# HydraBus_1_0_Rev1_2.net
KiCad netlist of a schematic drawn in EAGLE
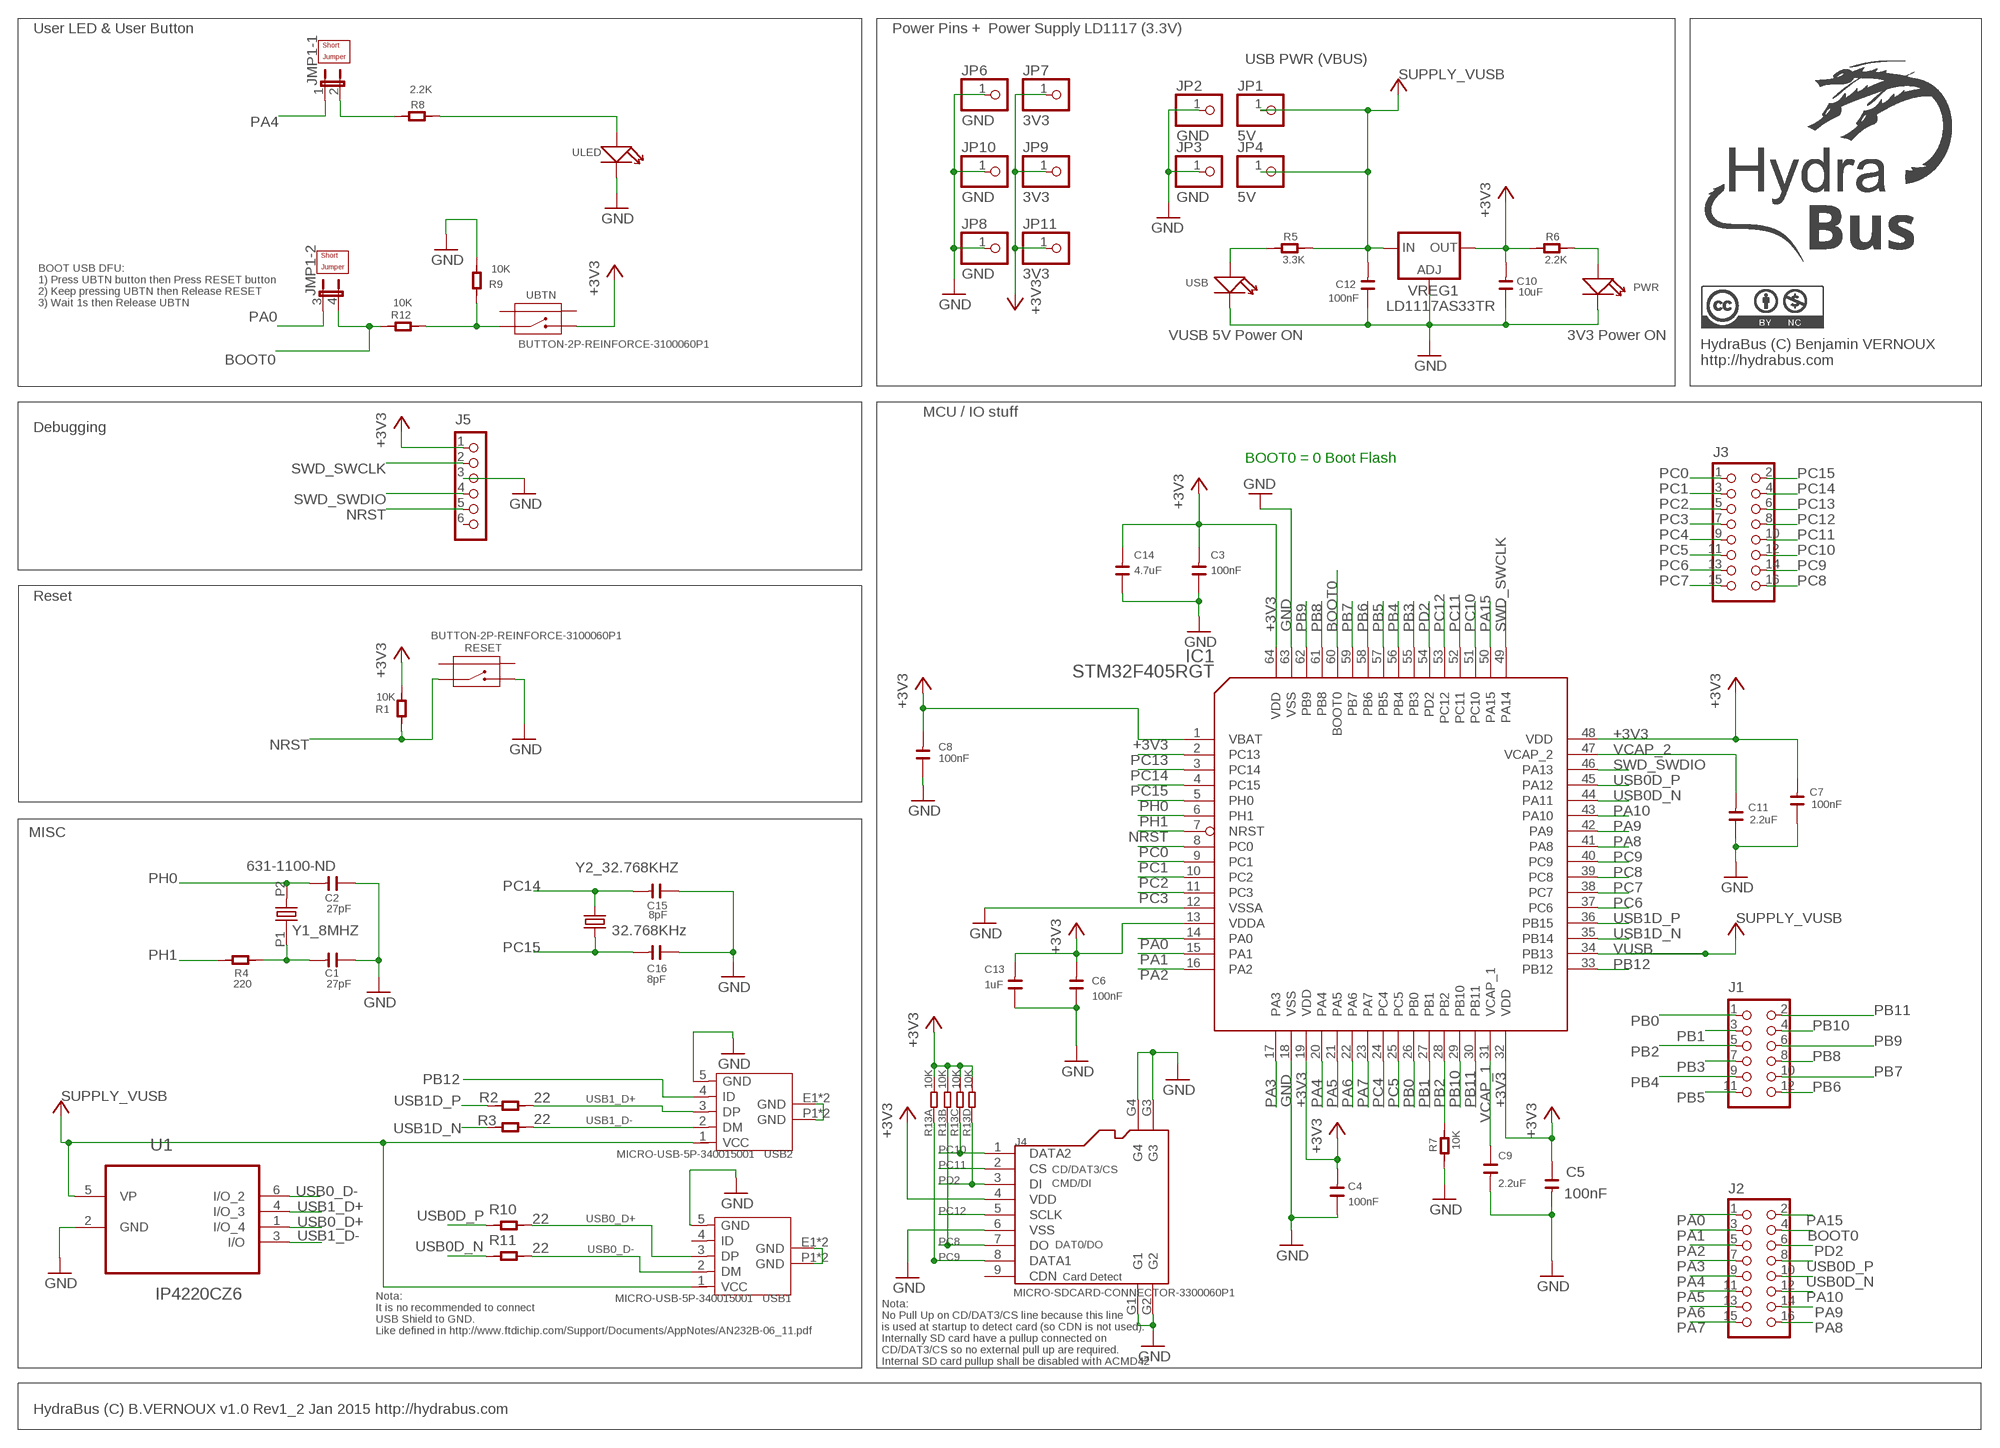
[diagram p0: schematic, sheet 1]

(export (version "E")
  (design (tool "Eeschema 10.0.6"))
  (components
    (comp (ref "C1")
      (value "27pF")
      (footprint "eagle-import:C0603")
      (libsource (lib "eagle-import") (part "C-0603"))
    )
    (comp (ref "C2")
      (value "27pF")
      (footprint "eagle-import:C0603")
      (libsource (lib "eagle-import") (part "C-0603"))
    )
    (comp (ref "C3")
      (value "100nF")
      (footprint "eagle-import:C0603")
      (libsource (lib "eagle-import") (part "C-0603"))
    )
    (comp (ref "C4")
      (value "100nF")
      (footprint "eagle-import:C0603")
      (libsource (lib "eagle-import") (part "C-0603"))
    )
    (comp (ref "C5")
      (value "100nF")
      (footprint "eagle-import:C0603")
      (libsource (lib "eagle-import") (part "C-0603"))
    )
    (comp (ref "C6")
      (value "100nF")
      (footprint "eagle-import:C0603")
      (libsource (lib "eagle-import") (part "C-0603"))
    )
    (comp (ref "C7")
      (value "100nF")
      (footprint "eagle-import:C0603")
      (libsource (lib "eagle-import") (part "C-0603"))
    )
    (comp (ref "C8")
      (value "100nF")
      (footprint "eagle-import:C0603")
      (libsource (lib "eagle-import") (part "C-0603"))
    )
    (comp (ref "C9")
      (value "2.2uF")
      (footprint "eagle-import:C0603")
      (libsource (lib "eagle-import") (part "C-0603"))
    )
    (comp (ref "C10")
      (value "10uF")
      (footprint "eagle-import:C0805")
      (libsource (lib "eagle-import") (part "C-0805"))
    )
    (comp (ref "C11")
      (value "2.2uF")
      (footprint "eagle-import:C0603")
      (libsource (lib "eagle-import") (part "C-0603"))
    )
    (comp (ref "C12")
      (value "100nF")
      (footprint "eagle-import:C0603")
      (libsource (lib "eagle-import") (part "C-0603"))
    )
    (comp (ref "C13")
      (value "1uF")
      (footprint "eagle-import:C0603")
      (libsource (lib "eagle-import") (part "C-0603"))
    )
    (comp (ref "C14")
      (value "4.7uF")
      (footprint "eagle-import:C0603")
      (libsource (lib "eagle-import") (part "C-0603"))
    )
    (comp (ref "C15")
      (value "8pF")
      (footprint "eagle-import:C0603")
      (libsource (lib "eagle-import") (part "C-0603"))
    )
    (comp (ref "C16")
      (value "8pF")
      (footprint "eagle-import:C0603")
      (libsource (lib "eagle-import") (part "C-0603"))
    )
    (comp (ref "IC1")
      (value "STM32F405RGT")
      (footprint "eagle-import:LQFP64")
      (libsource (lib "eagle-import") (part "STM32F405RTG"))
    )
    (comp (ref "J1")
      (value "CON_HEADER_2X06")
      (footprint "eagle-import:M2X6")
      (libsource (lib "eagle-import") (part "CON_HEADER_2X06"))
    )
    (comp (ref "J2")
      (value "CON_HEADER_2X08")
      (footprint "eagle-import:M2X8")
      (libsource (lib "eagle-import") (part "CON_HEADER_2X08"))
    )
    (comp (ref "J3")
      (value "CON_HEADER_2X08")
      (footprint "eagle-import:M2X8")
      (libsource (lib "eagle-import") (part "CON_HEADER_2X08"))
    )
    (comp (ref "J4")
      (value "MICRO-SDCARD-CONNECTOR-3300060P1")
      (footprint "eagle-import:9P-SMD-W-RING")
      (libsource (lib "eagle-import") (part "MICRO-SDCARD-CONNECTOR-3300060P1"))
    )
    (comp (ref "J5")
      (value "CON_HEADER_1X06-PTH")
      (footprint "eagle-import:M1X6")
      (libsource (lib "eagle-import") (part "CON_HEADER_1X06-PTH"))
    )
    (comp (ref "JMP1")
      (value "JP2QE")
      (footprint "eagle-import:JP2Q")
      (libsource (lib "eagle-import") (part "JP2QE"))
    )
    (comp (ref "JMP_UBTN")
      (value "SHORT-JUMPER-2P-3460440P1")
      (footprint "eagle-import:2P-2.54")
      (libsource (lib "eagle-import") (part "SHORT-JUMPER-2P-3460440P1"))
    )
    (comp (ref "JMP_ULED")
      (value "SHORT-JUMPER-2P-3460440P1")
      (footprint "eagle-import:2P-2.54")
      (libsource (lib "eagle-import") (part "SHORT-JUMPER-2P-3460440P1"))
    )
    (comp (ref "JP1")
      (value "5V")
      (footprint "eagle-import:1X01")
      (libsource (lib "eagle-import") (part "PINHD-1X1"))
    )
    (comp (ref "JP2")
      (value "GND")
      (footprint "eagle-import:1X01")
      (libsource (lib "eagle-import") (part "PINHD-1X1"))
    )
    (comp (ref "JP3")
      (value "GND")
      (footprint "eagle-import:1X01")
      (libsource (lib "eagle-import") (part "PINHD-1X1"))
    )
    (comp (ref "JP4")
      (value "5V")
      (footprint "eagle-import:1X01")
      (libsource (lib "eagle-import") (part "PINHD-1X1"))
    )
    (comp (ref "JP6")
      (value "GND")
      (footprint "eagle-import:1X01")
      (libsource (lib "eagle-import") (part "PINHD-1X1"))
    )
    (comp (ref "JP7")
      (value "3V3")
      (footprint "eagle-import:1X01")
      (libsource (lib "eagle-import") (part "PINHD-1X1"))
    )
    (comp (ref "JP8")
      (value "GND")
      (footprint "eagle-import:1X01")
      (libsource (lib "eagle-import") (part "PINHD-1X1"))
    )
    (comp (ref "JP9")
      (value "3V3")
      (footprint "eagle-import:1X01")
      (libsource (lib "eagle-import") (part "PINHD-1X1"))
    )
    (comp (ref "JP10")
      (value "GND")
      (footprint "eagle-import:1X01")
      (libsource (lib "eagle-import") (part "PINHD-1X1"))
    )
    (comp (ref "JP11")
      (value "3V3")
      (footprint "eagle-import:1X01")
      (libsource (lib "eagle-import") (part "PINHD-1X1"))
    )
    (comp (ref "PWR")
      (value "LED")
      (footprint "eagle-import:LED0603")
      (libsource (lib "eagle-import") (part "LED"))
    )
    (comp (ref "R1")
      (value "10K")
      (footprint "eagle-import:R0603")
      (libsource (lib "eagle-import") (part "R-0603"))
    )
    (comp (ref "R2")
      (value "22")
      (footprint "eagle-import:R0603")
      (libsource (lib "eagle-import") (part "R-0603"))
    )
    (comp (ref "R3")
      (value "22")
      (footprint "eagle-import:R0603")
      (libsource (lib "eagle-import") (part "R-0603"))
    )
    (comp (ref "R4")
      (value "220")
      (footprint "eagle-import:R0603")
      (libsource (lib "eagle-import") (part "R-0603"))
    )
    (comp (ref "R5")
      (value "3.3K")
      (footprint "eagle-import:R0603")
      (libsource (lib "eagle-import") (part "R-0603"))
    )
    (comp (ref "R6")
      (value "2.2K")
      (footprint "eagle-import:R0603")
      (libsource (lib "eagle-import") (part "R-0603"))
    )
    (comp (ref "R7")
      (value "10K")
      (footprint "eagle-import:R0603")
      (libsource (lib "eagle-import") (part "R-0603"))
    )
    (comp (ref "R8")
      (value "2.2K")
      (footprint "eagle-import:R0603")
      (libsource (lib "eagle-import") (part "R-0603"))
    )
    (comp (ref "R9")
      (value "10K")
      (footprint "eagle-import:R0603")
      (libsource (lib "eagle-import") (part "R-0603"))
    )
    (comp (ref "R10")
      (value "22")
      (footprint "eagle-import:R0603")
      (libsource (lib "eagle-import") (part "R-0603"))
    )
    (comp (ref "R11")
      (value "22")
      (footprint "eagle-import:R0603")
      (libsource (lib "eagle-import") (part "R-0603"))
    )
    (comp (ref "R12")
      (value "10K")
      (footprint "eagle-import:R0603")
      (libsource (lib "eagle-import") (part "R-0603"))
    )
    (comp (ref "R13")
      (value "10K")
      (footprint "eagle-import:R1206-8")
      (fields (field (name "OPL") "0040070P1 SMD RES ARRAY 10K OHM 4 RES 1206"))
      (libsource (lib "eagle-import") (part "R-4R"))
    )
    (comp (ref "RESET")
      (value "BUTTON-2P-REINFORCE-3100060P1")
      (footprint "eagle-import:4P-SMD-7.0X3.5X3.5H-90D")
      (libsource (lib "eagle-import") (part "BUTTON-2P-REINFORCE-3100060P1"))
    )
    (comp (ref "U1")
      (value "IP4220CZ6")
      (footprint "eagle-import:SOT95P275X110-6N")
      (libsource (lib "eagle-import") (part "IP4220CZ6"))
    )
    (comp (ref "UBTN")
      (value "BUTTON-2P-REINFORCE-3100060P1")
      (footprint "eagle-import:4P-SMD-7.0X3.5X3.5H-90D")
      (libsource (lib "eagle-import") (part "BUTTON-2P-REINFORCE-3100060P1"))
    )
    (comp (ref "ULED")
      (value "LED")
      (footprint "eagle-import:LED0603")
      (libsource (lib "eagle-import") (part "LED"))
    )
    (comp (ref "USB")
      (value "LED")
      (footprint "eagle-import:LED0603")
      (libsource (lib "eagle-import") (part "LED"))
    )
    (comp (ref "USB1")
      (value "MICRO-USB-5P-340015001")
      (footprint "eagle-import:B-SMD-5P")
      (libsource (lib "eagle-import") (part "MICRO-USB-5P-340015001"))
    )
    (comp (ref "USB2")
      (value "MICRO-USB-5P-340015001")
      (footprint "eagle-import:B-SMD-5P")
      (libsource (lib "eagle-import") (part "MICRO-USB-5P-340015001"))
    )
    (comp (ref "VREG1")
      (value "LD1117AS33TR")
      (footprint "eagle-import:SOT223")
      (libsource (lib "eagle-import") (part "LD117A?S33TR"))
    )
    (comp (ref "Y1_8MHZ")
      (value "631-1100-ND")
      (footprint "eagle-import:HC-49U-PTH")
      (libsource (lib "eagle-import") (part "OSC-XTAL-HC-49U-PTH"))
    )
    (comp (ref "Y2_32.768KHZ")
      (value "32.768KHz")
      (footprint "eagle-import:TC38H")
      (libsource (lib "eagle-import") (part "CRYSTALTC38H"))
    )
  )
  (nets
    (net (code "1") (name "+3V3") (class "Default")
      (node (ref "C10") (pin "1") (pinfunction "1_1") (pintype "bidirectional"))
      (node (ref "C13") (pin "1") (pinfunction "1_1") (pintype "bidirectional"))
      (node (ref "C14") (pin "1") (pinfunction "1_1") (pintype "bidirectional"))
      (node (ref "C3") (pin "1") (pinfunction "1_1") (pintype "bidirectional"))
      (node (ref "C4") (pin "1") (pinfunction "1_1") (pintype "bidirectional"))
      (node (ref "C5") (pin "2") (pinfunction "2_2") (pintype "bidirectional"))
      (node (ref "C6") (pin "1") (pinfunction "1_1") (pintype "bidirectional"))
      (node (ref "C7") (pin "1") (pinfunction "1_1") (pintype "bidirectional"))
      (node (ref "C8") (pin "1") (pinfunction "1_1") (pintype "bidirectional"))
      (node (ref "IC1") (pin "1") (pinfunction "VBAT_1") (pintype "power_in"))
      (node (ref "IC1") (pin "13") (pinfunction "VDDA_13") (pintype "power_in"))
      (node (ref "IC1") (pin "19") (pinfunction "VDD_19") (pintype "power_in"))
      (node (ref "IC1") (pin "32") (pinfunction "VDD_32") (pintype "power_in"))
      (node (ref "IC1") (pin "48") (pinfunction "VDD_48") (pintype "power_in"))
      (node (ref "IC1") (pin "64") (pinfunction "VDD_64") (pintype "power_in"))
      (node (ref "J4") (pin "4") (pinfunction "VDD_4") (pintype "bidirectional"))
      (node (ref "J5") (pin "1") (pinfunction "1_1") (pintype "bidirectional"))
      (node (ref "JP11") (pin "1") (pinfunction "1_1") (pintype "passive"))
      (node (ref "JP7") (pin "1") (pinfunction "1_1") (pintype "passive"))
      (node (ref "JP9") (pin "1") (pinfunction "1_1") (pintype "passive"))
      (node (ref "R1") (pin "2") (pinfunction "2_2") (pintype "bidirectional"))
      (node (ref "R13") (pin "5") (pinfunction "2_5") (pintype "passive"))
      (node (ref "R13") (pin "6") (pinfunction "2_6") (pintype "passive"))
      (node (ref "R13") (pin "7") (pinfunction "2_7") (pintype "passive"))
      (node (ref "R13") (pin "8") (pinfunction "2_8") (pintype "passive"))
      (node (ref "R6") (pin "2") (pinfunction "2_2") (pintype "bidirectional"))
      (node (ref "UBTN") (pin "2") (pinfunction "2_2") (pintype "bidirectional"))
      (node (ref "VREG1") (pin "4") (pinfunction "OUT_4") (pintype "passive"))
    )
    (net (code "2") (name "/BOOT0") (class "Default")
      (node (ref "IC1") (pin "60") (pinfunction "BOOT0_60") (pintype "bidirectional"))
      (node (ref "J2") (pin "4") (pinfunction "4_4") (pintype "passive"))
      (node (ref "JMP1") (pin "4") (pinfunction "2_4") (pintype "passive"))
      (node (ref "R12") (pin "2") (pinfunction "2_2") (pintype "bidirectional"))
    )
    (net (code "3") (name "/NRST") (class "Default")
      (node (ref "IC1") (pin "7") (pinfunction "NRST_7") (pintype "input"))
      (node (ref "J5") (pin "5") (pinfunction "5_5") (pintype "passive"))
      (node (ref "R1") (pin "1") (pinfunction "1_1") (pintype "bidirectional"))
      (node (ref "RESET") (pin "1") (pinfunction "1_1") (pintype "bidirectional"))
    )
    (net (code "4") (name "/PA0") (class "Default")
      (node (ref "IC1") (pin "14") (pinfunction "PA0_14") (pintype "bidirectional"))
      (node (ref "J2") (pin "1") (pinfunction "1_1") (pintype "passive"))
      (node (ref "JMP1") (pin "3") (pinfunction "1_3") (pintype "passive"))
    )
    (net (code "5") (name "/PA1") (class "Default")
      (node (ref "IC1") (pin "15") (pinfunction "PA1_15") (pintype "bidirectional"))
      (node (ref "J2") (pin "3") (pinfunction "3_3") (pintype "passive"))
    )
    (net (code "6") (name "/PA2") (class "Default")
      (node (ref "IC1") (pin "16") (pinfunction "PA2_16") (pintype "bidirectional"))
      (node (ref "J2") (pin "5") (pinfunction "5_5") (pintype "passive"))
    )
    (net (code "7") (name "/PA3") (class "Default")
      (node (ref "IC1") (pin "17") (pinfunction "PA3_17") (pintype "bidirectional"))
      (node (ref "J2") (pin "7") (pinfunction "7_7") (pintype "passive"))
    )
    (net (code "8") (name "/PA4") (class "Default")
      (node (ref "IC1") (pin "20") (pinfunction "PA4_20") (pintype "bidirectional"))
      (node (ref "J2") (pin "9") (pinfunction "9_9") (pintype "passive"))
      (node (ref "JMP1") (pin "1") (pinfunction "1_1") (pintype "passive"))
    )
    (net (code "9") (name "/PA5") (class "Default")
      (node (ref "IC1") (pin "21") (pinfunction "PA5_21") (pintype "bidirectional"))
      (node (ref "J2") (pin "11") (pinfunction "11_11") (pintype "passive"))
    )
    (net (code "10") (name "/PA6") (class "Default")
      (node (ref "IC1") (pin "22") (pinfunction "PA6_22") (pintype "bidirectional"))
      (node (ref "J2") (pin "13") (pinfunction "13_13") (pintype "passive"))
    )
    (net (code "11") (name "/PA7") (class "Default")
      (node (ref "IC1") (pin "23") (pinfunction "PA7_23") (pintype "bidirectional"))
      (node (ref "J2") (pin "15") (pinfunction "15_15") (pintype "passive"))
    )
    (net (code "12") (name "/PA8") (class "Default")
      (node (ref "IC1") (pin "41") (pinfunction "PA8_41") (pintype "bidirectional"))
      (node (ref "J2") (pin "16") (pinfunction "16_16") (pintype "passive"))
    )
    (net (code "13") (name "/PA9") (class "Default")
      (node (ref "IC1") (pin "42") (pinfunction "PA9_42") (pintype "bidirectional"))
      (node (ref "J2") (pin "14") (pinfunction "14_14") (pintype "passive"))
    )
    (net (code "14") (name "/PA10") (class "Default")
      (node (ref "IC1") (pin "43") (pinfunction "PA10_43") (pintype "bidirectional"))
      (node (ref "J2") (pin "12") (pinfunction "12_12") (pintype "passive"))
    )
    (net (code "15") (name "/PA15") (class "Default")
      (node (ref "IC1") (pin "50") (pinfunction "PA15_50") (pintype "bidirectional"))
      (node (ref "J2") (pin "2") (pinfunction "2_2") (pintype "passive"))
    )
    (net (code "16") (name "/PB0") (class "Default")
      (node (ref "IC1") (pin "26") (pinfunction "PB0_26") (pintype "bidirectional"))
      (node (ref "J1") (pin "1") (pinfunction "1_1") (pintype "passive"))
    )
    (net (code "17") (name "/PB1") (class "Default")
      (node (ref "IC1") (pin "27") (pinfunction "PB1_27") (pintype "bidirectional"))
      (node (ref "J1") (pin "3") (pinfunction "3_3") (pintype "passive"))
    )
    (net (code "18") (name "/PB2") (class "Default")
      (node (ref "IC1") (pin "28") (pinfunction "PB2_28") (pintype "bidirectional"))
      (node (ref "J1") (pin "5") (pinfunction "5_5") (pintype "passive"))
      (node (ref "R7") (pin "1") (pinfunction "1_1") (pintype "bidirectional"))
    )
    (net (code "19") (name "/PB3") (class "Default")
      (node (ref "IC1") (pin "55") (pinfunction "PB3_55") (pintype "bidirectional"))
      (node (ref "J1") (pin "7") (pinfunction "7_7") (pintype "passive"))
    )
    (net (code "20") (name "/PB4") (class "Default")
      (node (ref "IC1") (pin "56") (pinfunction "PB4_56") (pintype "bidirectional"))
      (node (ref "J1") (pin "9") (pinfunction "9_9") (pintype "passive"))
    )
    (net (code "21") (name "/PB5") (class "Default")
      (node (ref "IC1") (pin "57") (pinfunction "PB5_57") (pintype "bidirectional"))
      (node (ref "J1") (pin "11") (pinfunction "11_11") (pintype "passive"))
    )
    (net (code "22") (name "/PB6") (class "Default")
      (node (ref "IC1") (pin "58") (pinfunction "PB6_58") (pintype "bidirectional"))
      (node (ref "J1") (pin "12") (pinfunction "12_12") (pintype "passive"))
    )
    (net (code "23") (name "/PB7") (class "Default")
      (node (ref "IC1") (pin "59") (pinfunction "PB7_59") (pintype "bidirectional"))
      (node (ref "J1") (pin "10") (pinfunction "10_10") (pintype "passive"))
    )
    (net (code "24") (name "/PB8") (class "Default")
      (node (ref "IC1") (pin "61") (pinfunction "PB8_61") (pintype "bidirectional"))
      (node (ref "J1") (pin "8") (pinfunction "8_8") (pintype "passive"))
    )
    (net (code "25") (name "/PB9") (class "Default")
      (node (ref "IC1") (pin "62") (pinfunction "PB9_62") (pintype "bidirectional"))
      (node (ref "J1") (pin "6") (pinfunction "6_6") (pintype "passive"))
    )
    (net (code "26") (name "/PB10") (class "Default")
      (node (ref "IC1") (pin "29") (pinfunction "PB10_29") (pintype "bidirectional"))
      (node (ref "J1") (pin "4") (pinfunction "4_4") (pintype "passive"))
    )
    (net (code "27") (name "/PB11") (class "Default")
      (node (ref "IC1") (pin "30") (pinfunction "PB11_30") (pintype "bidirectional"))
      (node (ref "J1") (pin "2") (pinfunction "2_2") (pintype "passive"))
    )
    (net (code "28") (name "/PB12") (class "Default")
      (node (ref "IC1") (pin "33") (pinfunction "PB12_33") (pintype "bidirectional"))
      (node (ref "USB2") (pin "4") (pinfunction "ID_4") (pintype "bidirectional"))
    )
    (net (code "29") (name "/PC0") (class "Default")
      (node (ref "IC1") (pin "8") (pinfunction "PC0_8") (pintype "bidirectional"))
      (node (ref "J3") (pin "1") (pinfunction "1_1") (pintype "passive"))
    )
    (net (code "30") (name "/PC1") (class "Default")
      (node (ref "IC1") (pin "9") (pinfunction "PC1_9") (pintype "bidirectional"))
      (node (ref "J3") (pin "3") (pinfunction "3_3") (pintype "passive"))
    )
    (net (code "31") (name "/PC2") (class "Default")
      (node (ref "IC1") (pin "10") (pinfunction "PC2_10") (pintype "bidirectional"))
      (node (ref "J3") (pin "5") (pinfunction "5_5") (pintype "passive"))
    )
    (net (code "32") (name "/PC3") (class "Default")
      (node (ref "IC1") (pin "11") (pinfunction "PC3_11") (pintype "bidirectional"))
      (node (ref "J3") (pin "7") (pinfunction "7_7") (pintype "passive"))
    )
    (net (code "33") (name "/PC4") (class "Default")
      (node (ref "IC1") (pin "24") (pinfunction "PC4_24") (pintype "bidirectional"))
      (node (ref "J3") (pin "9") (pinfunction "9_9") (pintype "passive"))
    )
    (net (code "34") (name "/PC5") (class "Default")
      (node (ref "IC1") (pin "25") (pinfunction "PC5_25") (pintype "bidirectional"))
      (node (ref "J3") (pin "11") (pinfunction "11_11") (pintype "passive"))
    )
    (net (code "35") (name "/PC6") (class "Default")
      (node (ref "IC1") (pin "37") (pinfunction "PC6_37") (pintype "bidirectional"))
      (node (ref "J3") (pin "13") (pinfunction "13_13") (pintype "passive"))
    )
    (net (code "36") (name "/PC7") (class "Default")
      (node (ref "IC1") (pin "38") (pinfunction "PC7_38") (pintype "bidirectional"))
      (node (ref "J3") (pin "15") (pinfunction "15_15") (pintype "passive"))
    )
    (net (code "37") (name "/PC8") (class "Default")
      (node (ref "IC1") (pin "39") (pinfunction "PC8_39") (pintype "bidirectional"))
      (node (ref "J3") (pin "16") (pinfunction "16_16") (pintype "passive"))
      (node (ref "J4") (pin "7") (pinfunction "DO_7") (pintype "bidirectional"))
      (node (ref "R13") (pin "2") (pinfunction "1_2") (pintype "passive"))
    )
    (net (code "38") (name "/PC9") (class "Default")
      (node (ref "IC1") (pin "40") (pinfunction "PC9_40") (pintype "bidirectional"))
      (node (ref "J3") (pin "14") (pinfunction "14_14") (pintype "passive"))
      (node (ref "J4") (pin "8") (pinfunction "DATA1_8") (pintype "bidirectional"))
      (node (ref "R13") (pin "1") (pinfunction "1_1") (pintype "passive"))
    )
    (net (code "39") (name "/PC10") (class "Default")
      (node (ref "IC1") (pin "51") (pinfunction "PC10_51") (pintype "bidirectional"))
      (node (ref "J3") (pin "12") (pinfunction "12_12") (pintype "passive"))
      (node (ref "J4") (pin "1") (pinfunction "DATA2_1") (pintype "bidirectional"))
      (node (ref "R13") (pin "3") (pinfunction "1_3") (pintype "passive"))
    )
    (net (code "40") (name "/PC11") (class "Default")
      (node (ref "IC1") (pin "52") (pinfunction "PC11_52") (pintype "bidirectional"))
      (node (ref "J3") (pin "10") (pinfunction "10_10") (pintype "passive"))
      (node (ref "J4") (pin "2") (pinfunction "CS_2") (pintype "bidirectional"))
    )
    (net (code "41") (name "/PC12") (class "Default")
      (node (ref "IC1") (pin "53") (pinfunction "PC12_53") (pintype "bidirectional"))
      (node (ref "J3") (pin "8") (pinfunction "8_8") (pintype "passive"))
      (node (ref "J4") (pin "5") (pinfunction "SCLK_5") (pintype "bidirectional"))
    )
    (net (code "42") (name "/PC13") (class "Default")
      (node (ref "IC1") (pin "2") (pinfunction "PC13_2") (pintype "bidirectional"))
      (node (ref "J3") (pin "6") (pinfunction "6_6") (pintype "passive"))
    )
    (net (code "43") (name "/PC14") (class "Default")
      (node (ref "C15") (pin "1") (pinfunction "1_1") (pintype "bidirectional"))
      (node (ref "IC1") (pin "3") (pinfunction "PC14_3") (pintype "bidirectional"))
      (node (ref "J3") (pin "4") (pinfunction "4_4") (pintype "passive"))
      (node (ref "Y2_32.768KHZ") (pin "2") (pinfunction "2_2") (pintype "passive"))
    )
    (net (code "44") (name "/PC15") (class "Default")
      (node (ref "C16") (pin "1") (pinfunction "1_1") (pintype "bidirectional"))
      (node (ref "IC1") (pin "4") (pinfunction "PC15_4") (pintype "bidirectional"))
      (node (ref "J3") (pin "2") (pinfunction "2_2") (pintype "passive"))
      (node (ref "Y2_32.768KHZ") (pin "1") (pinfunction "1_1") (pintype "passive"))
    )
    (net (code "45") (name "/PD2") (class "Default")
      (node (ref "IC1") (pin "54") (pinfunction "PD2_54") (pintype "bidirectional"))
      (node (ref "J2") (pin "6") (pinfunction "6_6") (pintype "passive"))
      (node (ref "J4") (pin "3") (pinfunction "DI_3") (pintype "bidirectional"))
      (node (ref "R13") (pin "4") (pinfunction "1_4") (pintype "passive"))
    )
    (net (code "46") (name "/PH0") (class "Default")
      (node (ref "C2") (pin "1") (pinfunction "1_1") (pintype "bidirectional"))
      (node (ref "IC1") (pin "5") (pinfunction "PH0_5") (pintype "bidirectional"))
      (node (ref "Y1_8MHZ") (pin "P2") (pinfunction "2_P2") (pintype "passive"))
    )
    (net (code "47") (name "/PH1") (class "Default")
      (node (ref "IC1") (pin "6") (pinfunction "PH1_6") (pintype "bidirectional"))
      (node (ref "R4") (pin "2") (pinfunction "2_2") (pintype "bidirectional"))
    )
    (net (code "48") (name "/SWD_SWCLK") (class "Default")
      (node (ref "IC1") (pin "49") (pinfunction "PA14_49") (pintype "bidirectional"))
      (node (ref "J5") (pin "2") (pinfunction "2_2") (pintype "bidirectional"))
    )
    (net (code "49") (name "/SWD_SWDIO") (class "Default")
      (node (ref "IC1") (pin "46") (pinfunction "PA13_46") (pintype "bidirectional"))
      (node (ref "J5") (pin "4") (pinfunction "4_4") (pintype "passive"))
    )
    (net (code "50") (name "/USB0D_N") (class "Default")
      (node (ref "IC1") (pin "44") (pinfunction "PA11_44") (pintype "bidirectional"))
      (node (ref "J2") (pin "10") (pinfunction "10_10") (pintype "passive"))
      (node (ref "R11") (pin "2") (pinfunction "2_2") (pintype "bidirectional"))
    )
    (net (code "51") (name "/USB0D_P") (class "Default")
      (node (ref "IC1") (pin "45") (pinfunction "PA12_45") (pintype "bidirectional"))
      (node (ref "J2") (pin "8") (pinfunction "8_8") (pintype "passive"))
      (node (ref "R10") (pin "2") (pinfunction "2_2") (pintype "bidirectional"))
    )
    (net (code "52") (name "/USB0_D+") (class "Default")
      (node (ref "R10") (pin "1") (pinfunction "1_1") (pintype "bidirectional"))
      (node (ref "U1") (pin "1") (pinfunction "I/O_4_1") (pintype "bidirectional"))
      (node (ref "USB1") (pin "3") (pinfunction "DP_3") (pintype "bidirectional"))
    )
    (net (code "53") (name "/USB0_D-") (class "Default")
      (node (ref "R11") (pin "1") (pinfunction "1_1") (pintype "bidirectional"))
      (node (ref "U1") (pin "6") (pinfunction "I/O_2_6") (pintype "bidirectional"))
      (node (ref "USB1") (pin "2") (pinfunction "DM_2") (pintype "bidirectional"))
    )
    (net (code "54") (name "/USB1D_N") (class "Default")
      (node (ref "IC1") (pin "35") (pinfunction "PB14_35") (pintype "bidirectional"))
      (node (ref "R3") (pin "2") (pinfunction "2_2") (pintype "bidirectional"))
    )
    (net (code "55") (name "/USB1D_P") (class "Default")
      (node (ref "IC1") (pin "36") (pinfunction "PB15_36") (pintype "bidirectional"))
      (node (ref "R2") (pin "2") (pinfunction "2_2") (pintype "bidirectional"))
    )
    (net (code "56") (name "/USB1_D+") (class "Default")
      (node (ref "R2") (pin "1") (pinfunction "1_1") (pintype "bidirectional"))
      (node (ref "U1") (pin "4") (pinfunction "I/O_3_4") (pintype "bidirectional"))
      (node (ref "USB2") (pin "3") (pinfunction "DP_3") (pintype "bidirectional"))
    )
    (net (code "57") (name "/USB1_D-") (class "Default")
      (node (ref "R3") (pin "1") (pinfunction "1_1") (pintype "bidirectional"))
      (node (ref "U1") (pin "3") (pinfunction "I/O_3") (pintype "bidirectional"))
      (node (ref "USB2") (pin "2") (pinfunction "DM_2") (pintype "bidirectional"))
    )
    (net (code "58") (name "/VCAP_1") (class "Default")
      (node (ref "C9") (pin "2") (pinfunction "2_2") (pintype "bidirectional"))
      (node (ref "IC1") (pin "31") (pinfunction "VCAP_1_31") (pintype "passive"))
    )
    (net (code "59") (name "/VCAP_2") (class "Default")
      (node (ref "C11") (pin "1") (pinfunction "1_1") (pintype "bidirectional"))
      (node (ref "IC1") (pin "47") (pinfunction "VCAP_2_47") (pintype "passive"))
    )
    (net (code "60") (name "GND") (class "Default")
      (node (ref "C1") (pin "2") (pinfunction "2_2") (pintype "bidirectional"))
      (node (ref "C10") (pin "2") (pinfunction "2_2") (pintype "bidirectional"))
      (node (ref "C11") (pin "2") (pinfunction "2_2") (pintype "bidirectional"))
      (node (ref "C12") (pin "2") (pinfunction "2_2") (pintype "bidirectional"))
      (node (ref "C13") (pin "2") (pinfunction "2_2") (pintype "bidirectional"))
      (node (ref "C14") (pin "2") (pinfunction "2_2") (pintype "bidirectional"))
      (node (ref "C15") (pin "2") (pinfunction "2_2") (pintype "bidirectional"))
      (node (ref "C16") (pin "2") (pinfunction "2_2") (pintype "bidirectional"))
      (node (ref "C2") (pin "2") (pinfunction "2_2") (pintype "bidirectional"))
      (node (ref "C3") (pin "2") (pinfunction "2_2") (pintype "bidirectional"))
      (node (ref "C4") (pin "2") (pinfunction "2_2") (pintype "bidirectional"))
      (node (ref "C5") (pin "1") (pinfunction "1_1") (pintype "bidirectional"))
      (node (ref "C6") (pin "2") (pinfunction "2_2") (pintype "bidirectional"))
      (node (ref "C7") (pin "2") (pinfunction "2_2") (pintype "bidirectional"))
      (node (ref "C8") (pin "2") (pinfunction "2_2") (pintype "bidirectional"))
      (node (ref "C9") (pin "1") (pinfunction "1_1") (pintype "bidirectional"))
      (node (ref "IC1") (pin "12") (pinfunction "VSSA_12") (pintype "power_in"))
      (node (ref "IC1") (pin "18") (pinfunction "VSS_18") (pintype "power_in"))
      (node (ref "IC1") (pin "63") (pinfunction "VSS_63") (pintype "power_in"))
      (node (ref "J4") (pin "6") (pinfunction "VSS_6") (pintype "bidirectional"))
      (node (ref "J4") (pin "G1") (pinfunction "G1_G1") (pintype "bidirectional"))
      (node (ref "J4") (pin "G2") (pinfunction "G2_G2") (pintype "bidirectional"))
      (node (ref "J4") (pin "G3") (pinfunction "G3_G3") (pintype "bidirectional"))
      (node (ref "J4") (pin "G4") (pinfunction "G4_G4") (pintype "bidirectional"))
      (node (ref "J5") (pin "3") (pinfunction "3_3") (pintype "passive"))
      (node (ref "JP10") (pin "1") (pinfunction "1_1") (pintype "passive"))
      (node (ref "JP2") (pin "1") (pinfunction "1_1") (pintype "passive"))
      (node (ref "JP3") (pin "1") (pinfunction "1_1") (pintype "passive"))
      (node (ref "JP6") (pin "1") (pinfunction "1_1") (pintype "passive"))
      (node (ref "JP8") (pin "1") (pinfunction "1_1") (pintype "passive"))
      (node (ref "PWR") (pin "-") (pinfunction "-_-") (pintype "passive"))
      (node (ref "R7") (pin "2") (pinfunction "2_2") (pintype "bidirectional"))
      (node (ref "R9") (pin "2") (pinfunction "2_2") (pintype "bidirectional"))
      (node (ref "RESET") (pin "2") (pinfunction "2_2") (pintype "bidirectional"))
      (node (ref "U1") (pin "2") (pinfunction "GND_2") (pintype "passive"))
      (node (ref "ULED") (pin "-") (pinfunction "-_-") (pintype "passive"))
      (node (ref "USB") (pin "-") (pinfunction "-_-") (pintype "passive"))
      (node (ref "USB1") (pin "5") (pinfunction "GND_5") (pintype "bidirectional"))
      (node (ref "USB2") (pin "5") (pinfunction "GND_5") (pintype "bidirectional"))
      (node (ref "VREG1") (pin "1") (pinfunction "ADJ_1") (pintype "input"))
    )
    (net (code "61") (name "Net-(JMP1-Pad2)") (class "Default")
      (node (ref "JMP1") (pin "2") (pinfunction "2_2") (pintype "passive"))
      (node (ref "R8") (pin "2") (pinfunction "2_2") (pintype "bidirectional"))
    )
    (net (code "62") (name "Net-(PWR-Pad+)") (class "Default")
      (node (ref "PWR") (pin "+") (pinfunction "+_+") (pintype "passive"))
      (node (ref "R6") (pin "1") (pinfunction "1_1") (pintype "bidirectional"))
    )
    (net (code "63") (name "Net-(R5-Pad2)") (class "Default")
      (node (ref "R5") (pin "2") (pinfunction "2_2") (pintype "bidirectional"))
      (node (ref "USB") (pin "+") (pinfunction "+_+") (pintype "passive"))
    )
    (net (code "64") (name "Net-(R8-Pad1)") (class "Default")
      (node (ref "R8") (pin "1") (pinfunction "1_1") (pintype "bidirectional"))
      (node (ref "ULED") (pin "+") (pinfunction "+_+") (pintype "passive"))
    )
    (net (code "65") (name "Net-(R12-Pad1)") (class "Default")
      (node (ref "R12") (pin "1") (pinfunction "1_1") (pintype "bidirectional"))
      (node (ref "R9") (pin "1") (pinfunction "1_1") (pintype "bidirectional"))
      (node (ref "UBTN") (pin "1") (pinfunction "1_1") (pintype "bidirectional"))
    )
    (net (code "66") (name "Net-(USB1-GND-PadE1)") (class "Default")
      (node (ref "USB1") (pin "E1") (pinfunction "GND_E1") (pintype "bidirectional"))
      (node (ref "USB1") (pin "E2") (pinfunction "GND_E2") (pintype "bidirectional"))
      (node (ref "USB1") (pin "P1") (pinfunction "GND_P1") (pintype "bidirectional"))
      (node (ref "USB1") (pin "P2") (pinfunction "GND_P2") (pintype "bidirectional"))
    )
    (net (code "67") (name "Net-(USB2-GND-PadE1)") (class "Default")
      (node (ref "USB2") (pin "E1") (pinfunction "GND_E1") (pintype "bidirectional"))
      (node (ref "USB2") (pin "E2") (pinfunction "GND_E2") (pintype "bidirectional"))
      (node (ref "USB2") (pin "P1") (pinfunction "GND_P1") (pintype "bidirectional"))
      (node (ref "USB2") (pin "P2") (pinfunction "GND_P2") (pintype "bidirectional"))
    )
    (net (code "68") (name "Net-(Y1_8MHZ-1)") (class "Default")
      (node (ref "C1") (pin "1") (pinfunction "1_1") (pintype "bidirectional"))
      (node (ref "R4") (pin "1") (pinfunction "1_1") (pintype "bidirectional"))
      (node (ref "Y1_8MHZ") (pin "P1") (pinfunction "1_P1") (pintype "passive"))
    )
    (net (code "69") (name "SUPPLY_VUSB") (class "Default")
      (node (ref "C12") (pin "1") (pinfunction "1_1") (pintype "bidirectional"))
      (node (ref "IC1") (pin "34") (pinfunction "PB13_34") (pintype "bidirectional"))
      (node (ref "JP1") (pin "1") (pinfunction "1_1") (pintype "passive"))
      (node (ref "JP4") (pin "1") (pinfunction "1_1") (pintype "passive"))
      (node (ref "R5") (pin "1") (pinfunction "1_1") (pintype "bidirectional"))
      (node (ref "U1") (pin "5") (pinfunction "VP_5") (pintype "power_in"))
      (node (ref "USB1") (pin "1") (pinfunction "VCC_1") (pintype "bidirectional"))
      (node (ref "USB2") (pin "1") (pinfunction "VCC_1") (pintype "bidirectional"))
      (node (ref "VREG1") (pin "3") (pinfunction "IN_3") (pintype "input"))
    )
    (net (code "70") (name "unconnected-(J4-CDN-Pad9)") (class "Default")
      (node (ref "J4") (pin "9") (pinfunction "CDN_9") (pintype "bidirectional"))
    )
    (net (code "71") (name "unconnected-(J5-Pad6)") (class "Default")
      (node (ref "J5") (pin "6") (pinfunction "6_6") (pintype "passive"))
    )
    (net (code "72") (name "unconnected-(RESET-PadS1)") (class "Default")
      (node (ref "RESET") (pin "S1") (pinfunction "S1_S1") (pintype "bidirectional"))
    )
    (net (code "73") (name "unconnected-(RESET-PadS2)") (class "Default")
      (node (ref "RESET") (pin "S2") (pinfunction "S2_S2") (pintype "bidirectional"))
    )
    (net (code "74") (name "unconnected-(UBTN-PadS1)") (class "Default")
      (node (ref "UBTN") (pin "S1") (pinfunction "S1_S1") (pintype "bidirectional"))
    )
    (net (code "75") (name "unconnected-(UBTN-PadS2)") (class "Default")
      (node (ref "UBTN") (pin "S2") (pinfunction "S2_S2") (pintype "bidirectional"))
    )
    (net (code "76") (name "unconnected-(USB1-ID-Pad4)") (class "Default")
      (node (ref "USB1") (pin "4") (pinfunction "ID_4") (pintype "bidirectional"))
    )
  )
)
